# SCH_n2_pdb_v4_2022-03-22.net
KiCad netlist of a schematic drawn in EasyEDA
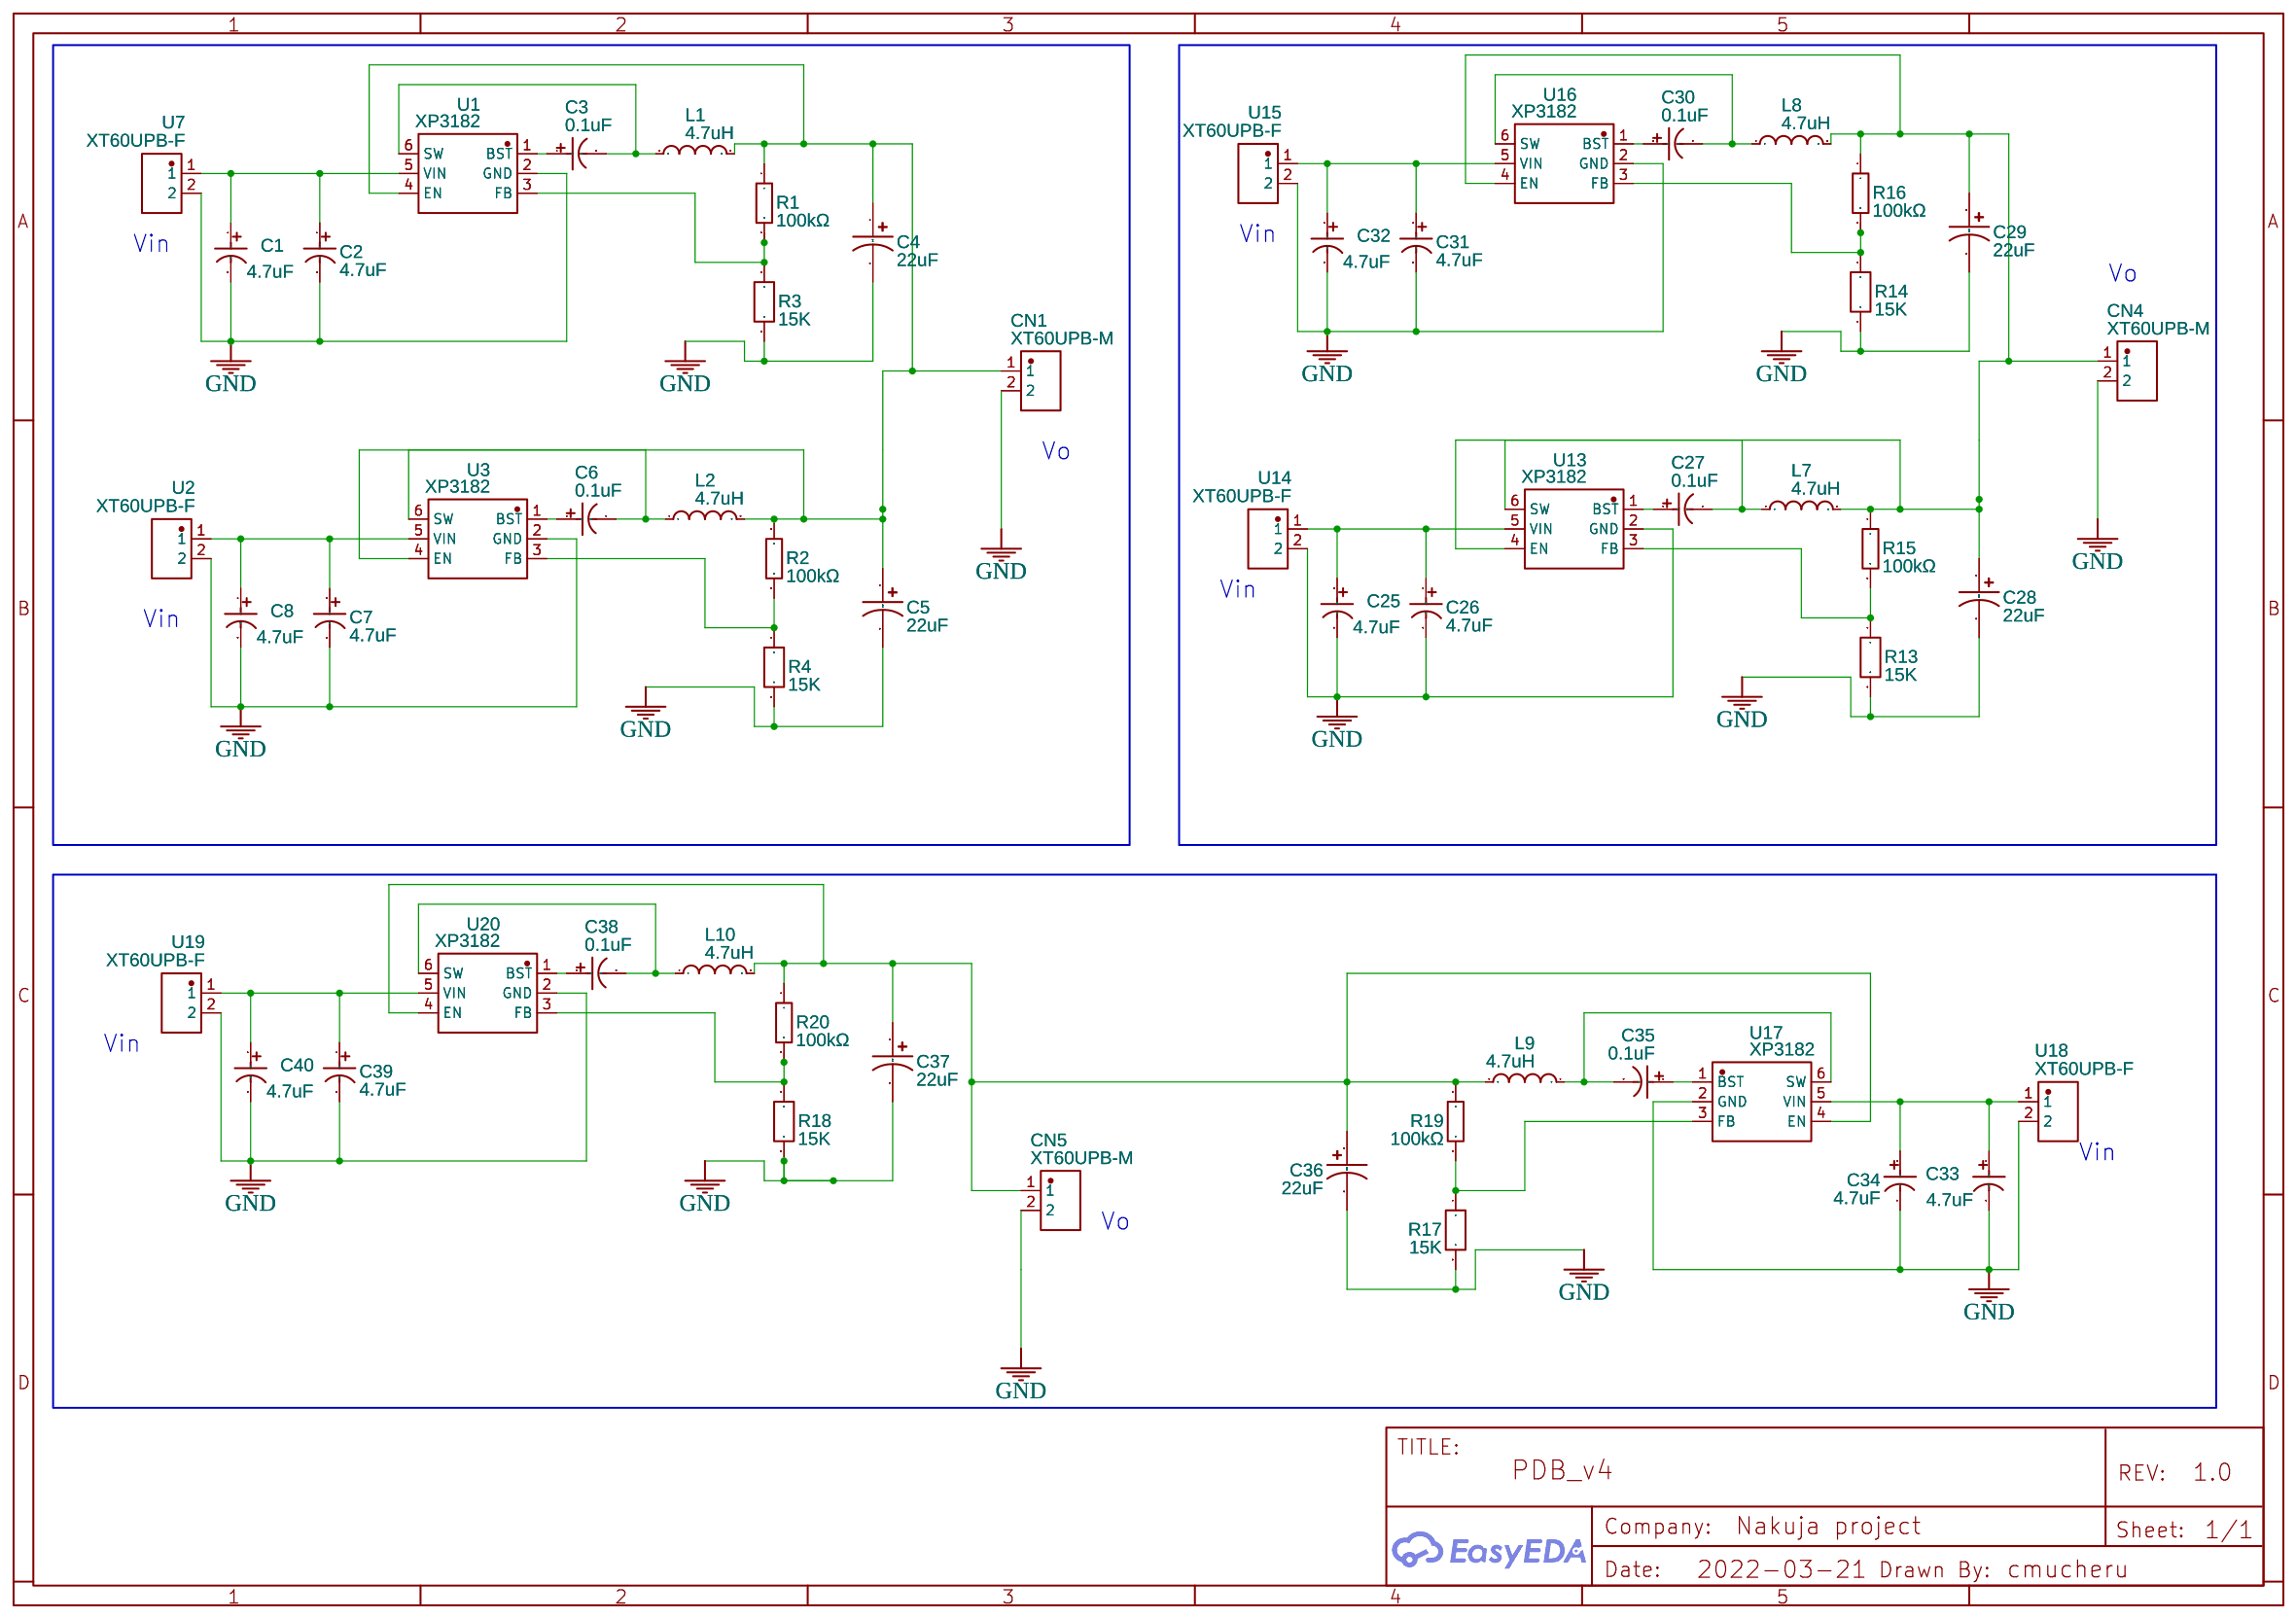
[diagram p0: schematic sheet]

(export (version "E")
  (design (tool "Eeschema 10.0.6"))
  (components
    (comp (ref "C1")
      (value "4.7uF")
      (fields
        (field (name "BOM_Manufacturer Part") "ERK2GM4R7F09OT")
        (field (name "BOM_Supplier Part") "C112499")
      )
      (libsource (lib "") (part "ERK2GM4R7F09OT"))
    )
    (comp (ref "C2")
      (value "4.7uF")
      (fields
        (field (name "BOM_Manufacturer Part") "ERK2GM4R7F09OT")
        (field (name "BOM_Supplier Part") "C112499")
      )
      (libsource (lib "") (part "ERK2GM4R7F09OT"))
    )
    (comp (ref "C3")
      (value "0.1uF")
      (fields
        (field (name "BOM_Manufacturer Part") "0.1uF 50V 4*5 Black high frequency")
        (field (name "BOM_Supplier Part") "C45093")
      )
      (libsource (lib "") (part "0.1uF 50V 4*5 Black high frequency"))
    )
    (comp (ref "C4")
      (value "22uF")
      (fields
        (field (name "BOM_Manufacturer Part") "400AX22MEFC12.5X16")
        (field (name "BOM_Supplier Part") "C473193")
      )
      (libsource (lib "") (part "400AX22MEFC12.5X16"))
    )
    (comp (ref "C5")
      (value "22uF")
      (fields
        (field (name "BOM_Manufacturer Part") "400AX22MEFC12.5X16")
        (field (name "BOM_Supplier Part") "C473193")
      )
      (libsource (lib "") (part "400AX22MEFC12.5X16"))
    )
    (comp (ref "C6")
      (value "0.1uF")
      (fields
        (field (name "BOM_Manufacturer Part") "0.1uF 50V 4*5 Black high frequency")
        (field (name "BOM_Supplier Part") "C45093")
      )
      (libsource (lib "") (part "0.1uF 50V 4*5 Black high frequency"))
    )
    (comp (ref "C7")
      (value "4.7uF")
      (fields
        (field (name "BOM_Manufacturer Part") "ERK2GM4R7F09OT")
        (field (name "BOM_Supplier Part") "C112499")
      )
      (libsource (lib "") (part "ERK2GM4R7F09OT"))
    )
    (comp (ref "C8")
      (value "4.7uF")
      (fields
        (field (name "BOM_Manufacturer Part") "ERK2GM4R7F09OT")
        (field (name "BOM_Supplier Part") "C112499")
      )
      (libsource (lib "") (part "ERK2GM4R7F09OT"))
    )
    (comp (ref "C25")
      (value "4.7uF")
      (fields
        (field (name "BOM_Manufacturer Part") "ERK2GM4R7F09OT")
        (field (name "BOM_Supplier Part") "C112499")
      )
      (libsource (lib "") (part "ERK2GM4R7F09OT"))
    )
    (comp (ref "C26")
      (value "4.7uF")
      (fields
        (field (name "BOM_Manufacturer Part") "ERK2GM4R7F09OT")
        (field (name "BOM_Supplier Part") "C112499")
      )
      (libsource (lib "") (part "ERK2GM4R7F09OT"))
    )
    (comp (ref "C27")
      (value "0.1uF")
      (fields
        (field (name "BOM_Manufacturer Part") "0.1uF 50V 4*5 Black high frequency")
        (field (name "BOM_Supplier Part") "C45093")
      )
      (libsource (lib "") (part "0.1uF 50V 4*5 Black high frequency"))
    )
    (comp (ref "C28")
      (value "22uF")
      (fields
        (field (name "BOM_Manufacturer Part") "400AX22MEFC12.5X16")
        (field (name "BOM_Supplier Part") "C473193")
      )
      (libsource (lib "") (part "400AX22MEFC12.5X16"))
    )
    (comp (ref "C29")
      (value "22uF")
      (fields
        (field (name "BOM_Manufacturer Part") "400AX22MEFC12.5X16")
        (field (name "BOM_Supplier Part") "C473193")
      )
      (libsource (lib "") (part "400AX22MEFC12.5X16"))
    )
    (comp (ref "C30")
      (value "0.1uF")
      (fields
        (field (name "BOM_Manufacturer Part") "0.1uF 50V 4*5 Black high frequency")
        (field (name "BOM_Supplier Part") "C45093")
      )
      (libsource (lib "") (part "0.1uF 50V 4*5 Black high frequency"))
    )
    (comp (ref "C31")
      (value "4.7uF")
      (fields
        (field (name "BOM_Manufacturer Part") "ERK2GM4R7F09OT")
        (field (name "BOM_Supplier Part") "C112499")
      )
      (libsource (lib "") (part "ERK2GM4R7F09OT"))
    )
    (comp (ref "C32")
      (value "4.7uF")
      (fields
        (field (name "BOM_Manufacturer Part") "ERK2GM4R7F09OT")
        (field (name "BOM_Supplier Part") "C112499")
      )
      (libsource (lib "") (part "ERK2GM4R7F09OT"))
    )
    (comp (ref "C33")
      (value "4.7uF")
      (fields
        (field (name "BOM_Manufacturer Part") "ERK2GM4R7F09OT")
        (field (name "BOM_Supplier Part") "C112499")
      )
      (libsource (lib "") (part "ERK2GM4R7F09OT_1"))
    )
    (comp (ref "C34")
      (value "4.7uF")
      (fields
        (field (name "BOM_Manufacturer Part") "ERK2GM4R7F09OT")
        (field (name "BOM_Supplier Part") "C112499")
      )
      (libsource (lib "") (part "ERK2GM4R7F09OT_1"))
    )
    (comp (ref "C35")
      (value "0.1uF")
      (fields
        (field (name "BOM_Manufacturer Part") "0.1uF 50V 4*5 Black high frequency")
        (field (name "BOM_Supplier Part") "C45093")
      )
      (libsource (lib "") (part "0.1uF 50V 4*5 Black high frequency_1"))
    )
    (comp (ref "C36")
      (value "22uF")
      (fields
        (field (name "BOM_Manufacturer Part") "400AX22MEFC12.5X16")
        (field (name "BOM_Supplier Part") "C473193")
      )
      (libsource (lib "") (part "400AX22MEFC12.5X16_1"))
    )
    (comp (ref "C37")
      (value "22uF")
      (fields
        (field (name "BOM_Manufacturer Part") "400AX22MEFC12.5X16")
        (field (name "BOM_Supplier Part") "C473193")
      )
      (libsource (lib "") (part "400AX22MEFC12.5X16"))
    )
    (comp (ref "C38")
      (value "0.1uF")
      (fields
        (field (name "BOM_Manufacturer Part") "0.1uF 50V 4*5 Black high frequency")
        (field (name "BOM_Supplier Part") "C45093")
      )
      (libsource (lib "") (part "0.1uF 50V 4*5 Black high frequency"))
    )
    (comp (ref "C39")
      (value "4.7uF")
      (fields
        (field (name "BOM_Manufacturer Part") "ERK2GM4R7F09OT")
        (field (name "BOM_Supplier Part") "C112499")
      )
      (libsource (lib "") (part "ERK2GM4R7F09OT"))
    )
    (comp (ref "C40")
      (value "4.7uF")
      (fields
        (field (name "BOM_Manufacturer Part") "ERK2GM4R7F09OT")
        (field (name "BOM_Supplier Part") "C112499")
      )
      (libsource (lib "") (part "ERK2GM4R7F09OT"))
    )
    (comp (ref "CN1")
      (value "XT60UPB-M")
      (fields (field (name "BOM_Supplier Part") "C2918078"))
      (libsource (lib "") (part "XT60UPB-M"))
    )
    (comp (ref "CN4")
      (value "XT60UPB-M")
      (fields (field (name "BOM_Supplier Part") "C2918078"))
      (libsource (lib "") (part "XT60UPB-M"))
    )
    (comp (ref "CN5")
      (value "XT60UPB-M")
      (fields (field (name "BOM_Supplier Part") "C2918078"))
      (libsource (lib "") (part "XT60UPB-M"))
    )
    (comp (ref "L1")
      (value "4.7uH")
      (fields
        (field (name "BOM_Manufacturer Part") "MCS0530-4R7MN2")
        (field (name "BOM_Supplier Part") "C2836880")
      )
      (libsource (lib "") (part "MCS0530-4R7MN2_1"))
    )
    (comp (ref "L2")
      (value "4.7uH")
      (fields
        (field (name "BOM_Manufacturer Part") "MCS0530-4R7MN2")
        (field (name "BOM_Supplier Part") "C2836880")
      )
      (libsource (lib "") (part "MCS0530-4R7MN2_1"))
    )
    (comp (ref "L7")
      (value "4.7uH")
      (fields
        (field (name "BOM_Manufacturer Part") "MCS0530-4R7MN2")
        (field (name "BOM_Supplier Part") "C2836880")
      )
      (libsource (lib "") (part "MCS0530-4R7MN2_1"))
    )
    (comp (ref "L8")
      (value "4.7uH")
      (fields
        (field (name "BOM_Manufacturer Part") "MCS0530-4R7MN2")
        (field (name "BOM_Supplier Part") "C2836880")
      )
      (libsource (lib "") (part "MCS0530-4R7MN2_1"))
    )
    (comp (ref "L9")
      (value "4.7uH")
      (fields
        (field (name "BOM_Manufacturer Part") "MCS0530-4R7MN2")
        (field (name "BOM_Supplier Part") "C2836880")
      )
      (libsource (lib "") (part "MCS0530-4R7MN2"))
    )
    (comp (ref "L10")
      (value "4.7uH")
      (fields
        (field (name "BOM_Manufacturer Part") "MCS0530-4R7MN2")
        (field (name "BOM_Supplier Part") "C2836880")
      )
      (libsource (lib "") (part "MCS0530-4R7MN2_1"))
    )
    (comp (ref "R1")
      (value "100kΩ")
      (fields
        (field (name "BOM_Manufacturer Part") "AR02BTD1003")
        (field (name "BOM_Supplier Part") "C319965")
      )
      (libsource (lib "") (part "AR02BTD1003"))
    )
    (comp (ref "R2")
      (value "100kΩ")
      (fields
        (field (name "BOM_Manufacturer Part") "AR02BTD1003")
        (field (name "BOM_Supplier Part") "C319965")
      )
      (libsource (lib "") (part "AR02BTD1003"))
    )
    (comp (ref "R3")
      (value "15K")
      (fields
        (field (name "BOM_Manufacturer Part") "TC0525D1502T5E")
        (field (name "BOM_Supplier Part") "C44536")
      )
      (libsource (lib "") (part "TC0525D1502T5E_C44536"))
    )
    (comp (ref "R4")
      (value "15K")
      (fields
        (field (name "BOM_Manufacturer Part") "TC0525D1502T5E")
        (field (name "BOM_Supplier Part") "C44536")
      )
      (libsource (lib "") (part "TC0525D1502T5E_C44536"))
    )
    (comp (ref "R13")
      (value "15K")
      (fields
        (field (name "BOM_Manufacturer Part") "TC0525D1502T5E")
        (field (name "BOM_Supplier Part") "C44536")
      )
      (libsource (lib "") (part "TC0525D1502T5E_C44536"))
    )
    (comp (ref "R14")
      (value "15K")
      (fields
        (field (name "BOM_Manufacturer Part") "TC0525D1502T5E")
        (field (name "BOM_Supplier Part") "C44536")
      )
      (libsource (lib "") (part "TC0525D1502T5E_C44536"))
    )
    (comp (ref "R15")
      (value "100kΩ")
      (fields
        (field (name "BOM_Manufacturer Part") "AR02BTD1003")
        (field (name "BOM_Supplier Part") "C319965")
      )
      (libsource (lib "") (part "AR02BTD1003"))
    )
    (comp (ref "R16")
      (value "100kΩ")
      (fields
        (field (name "BOM_Manufacturer Part") "AR02BTD1003")
        (field (name "BOM_Supplier Part") "C319965")
      )
      (libsource (lib "") (part "AR02BTD1003"))
    )
    (comp (ref "R17")
      (value "15K")
      (fields
        (field (name "BOM_Manufacturer Part") "TC0525D1502T5E")
        (field (name "BOM_Supplier Part") "C44536")
      )
      (libsource (lib "") (part "TC0525D1502T5E_C44536"))
    )
    (comp (ref "R18")
      (value "15K")
      (fields
        (field (name "BOM_Manufacturer Part") "TC0525D1502T5E")
        (field (name "BOM_Supplier Part") "C44536")
      )
      (libsource (lib "") (part "TC0525D1502T5E_C44536"))
    )
    (comp (ref "R19")
      (value "100kΩ")
      (fields
        (field (name "BOM_Manufacturer Part") "AR02BTD1003")
        (field (name "BOM_Supplier Part") "C319965")
      )
      (libsource (lib "") (part "AR02BTD1003"))
    )
    (comp (ref "R20")
      (value "100kΩ")
      (fields
        (field (name "BOM_Manufacturer Part") "AR02BTD1003")
        (field (name "BOM_Supplier Part") "C319965")
      )
      (libsource (lib "") (part "AR02BTD1003"))
    )
    (comp (ref "U1")
      (value "XP3182")
      (fields (field (name "BOM_Supplier Part") "C2802261"))
      (libsource (lib "") (part "XP3182"))
    )
    (comp (ref "U2")
      (value "XT60UPB-F")
      (fields (field (name "BOM_Supplier Part") "C9900007500"))
      (libsource (lib "") (part "XT60UPB-F"))
    )
    (comp (ref "U3")
      (value "XP3182")
      (fields (field (name "BOM_Supplier Part") "C2802261"))
      (libsource (lib "") (part "XP3182"))
    )
    (comp (ref "U7")
      (value "XT60UPB-F")
      (fields (field (name "BOM_Supplier Part") "C9900007500"))
      (libsource (lib "") (part "XT60UPB-F"))
    )
    (comp (ref "U13")
      (value "XP3182")
      (fields (field (name "BOM_Supplier Part") "C2802261"))
      (libsource (lib "") (part "XP3182"))
    )
    (comp (ref "U14")
      (value "XT60UPB-F")
      (fields (field (name "BOM_Supplier Part") "C9900007500"))
      (libsource (lib "") (part "XT60UPB-F"))
    )
    (comp (ref "U15")
      (value "XT60UPB-F")
      (fields (field (name "BOM_Supplier Part") "C9900007500"))
      (libsource (lib "") (part "XT60UPB-F"))
    )
    (comp (ref "U16")
      (value "XP3182")
      (fields (field (name "BOM_Supplier Part") "C2802261"))
      (libsource (lib "") (part "XP3182"))
    )
    (comp (ref "U17")
      (value "XP3182")
      (fields (field (name "BOM_Supplier Part") "C2802261"))
      (libsource (lib "") (part "XP3182_1"))
    )
    (comp (ref "U18")
      (value "XT60UPB-F")
      (fields (field (name "BOM_Supplier Part") "C9900007500"))
      (libsource (lib "") (part "XT60UPB-F_1"))
    )
    (comp (ref "U19")
      (value "XT60UPB-F")
      (fields (field (name "BOM_Supplier Part") "C9900007500"))
      (libsource (lib "") (part "XT60UPB-F"))
    )
    (comp (ref "U20")
      (value "XP3182")
      (fields (field (name "BOM_Supplier Part") "C2802261"))
      (libsource (lib "") (part "XP3182"))
    )
  )
  (nets
    (net (code "1") (name "GND") (class "Default")
      (node (ref "C1") (pin "2") (pinfunction "2_2") (pintype "input"))
      (node (ref "C2") (pin "2") (pinfunction "2_2") (pintype "input"))
      (node (ref "C25") (pin "2") (pinfunction "2_2") (pintype "input"))
      (node (ref "C26") (pin "2") (pinfunction "2_2") (pintype "input"))
      (node (ref "C28") (pin "2") (pinfunction "2_2") (pintype "unspecified"))
      (node (ref "C29") (pin "2") (pinfunction "2_2") (pintype "unspecified"))
      (node (ref "C31") (pin "2") (pinfunction "2_2") (pintype "input"))
      (node (ref "C32") (pin "2") (pinfunction "2_2") (pintype "input"))
      (node (ref "C33") (pin "2") (pinfunction "2_2") (pintype "input"))
      (node (ref "C34") (pin "2") (pinfunction "2_2") (pintype "input"))
      (node (ref "C36") (pin "2") (pinfunction "2_2") (pintype "unspecified"))
      (node (ref "C37") (pin "2") (pinfunction "2_2") (pintype "unspecified"))
      (node (ref "C39") (pin "2") (pinfunction "2_2") (pintype "input"))
      (node (ref "C4") (pin "2") (pinfunction "2_2") (pintype "unspecified"))
      (node (ref "C40") (pin "2") (pinfunction "2_2") (pintype "input"))
      (node (ref "C5") (pin "2") (pinfunction "2_2") (pintype "unspecified"))
      (node (ref "C7") (pin "2") (pinfunction "2_2") (pintype "input"))
      (node (ref "C8") (pin "2") (pinfunction "2_2") (pintype "input"))
      (node (ref "CN1") (pin "2") (pinfunction "2_2") (pintype "unspecified"))
      (node (ref "CN4") (pin "2") (pinfunction "2_2") (pintype "unspecified"))
      (node (ref "CN5") (pin "2") (pinfunction "2_2") (pintype "unspecified"))
      (node (ref "R13") (pin "2") (pinfunction "2_2") (pintype "unspecified"))
      (node (ref "R14") (pin "2") (pinfunction "2_2") (pintype "unspecified"))
      (node (ref "R17") (pin "2") (pinfunction "2_2") (pintype "unspecified"))
      (node (ref "R18") (pin "2") (pinfunction "2_2") (pintype "unspecified"))
      (node (ref "R3") (pin "2") (pinfunction "2_2") (pintype "unspecified"))
      (node (ref "R4") (pin "2") (pinfunction "2_2") (pintype "unspecified"))
      (node (ref "U1") (pin "2") (pinfunction "GND_2") (pintype "unspecified"))
      (node (ref "U13") (pin "2") (pinfunction "GND_2") (pintype "unspecified"))
      (node (ref "U14") (pin "2") (pinfunction "2_2") (pintype "unspecified"))
      (node (ref "U15") (pin "2") (pinfunction "2_2") (pintype "unspecified"))
      (node (ref "U16") (pin "2") (pinfunction "GND_2") (pintype "unspecified"))
      (node (ref "U17") (pin "2") (pinfunction "GND_2") (pintype "unspecified"))
      (node (ref "U18") (pin "2") (pinfunction "2_2") (pintype "unspecified"))
      (node (ref "U19") (pin "2") (pinfunction "2_2") (pintype "unspecified"))
      (node (ref "U2") (pin "2") (pinfunction "2_2") (pintype "unspecified"))
      (node (ref "U20") (pin "2") (pinfunction "GND_2") (pintype "unspecified"))
      (node (ref "U3") (pin "2") (pinfunction "GND_2") (pintype "unspecified"))
      (node (ref "U7") (pin "2") (pinfunction "2_2") (pintype "unspecified"))
    )
    (net (code "2") (name "Net-(U1-BST)") (class "Default")
      (node (ref "C3") (pin "1") (pinfunction "1_1") (pintype "input"))
      (node (ref "U1") (pin "1") (pinfunction "BST_1") (pintype "unspecified"))
    )
    (net (code "3") (name "Net-(U1-EN)") (class "Default")
      (node (ref "C4") (pin "1") (pinfunction "1_1") (pintype "unspecified"))
      (node (ref "C5") (pin "1") (pinfunction "1_1") (pintype "unspecified"))
      (node (ref "CN1") (pin "1") (pinfunction "1_1") (pintype "unspecified"))
      (node (ref "L1") (pin "2") (pinfunction "2_2") (pintype "unspecified"))
      (node (ref "L2") (pin "2") (pinfunction "2_2") (pintype "unspecified"))
      (node (ref "R1") (pin "1") (pinfunction "1_1") (pintype "unspecified"))
      (node (ref "R2") (pin "1") (pinfunction "1_1") (pintype "unspecified"))
      (node (ref "U1") (pin "4") (pinfunction "EN_4") (pintype "unspecified"))
      (node (ref "U3") (pin "4") (pinfunction "EN_4") (pintype "unspecified"))
    )
    (net (code "4") (name "Net-(U1-FB)") (class "Default")
      (node (ref "R1") (pin "2") (pinfunction "2_2") (pintype "unspecified"))
      (node (ref "R3") (pin "1") (pinfunction "1_1") (pintype "unspecified"))
      (node (ref "U1") (pin "3") (pinfunction "FB_3") (pintype "unspecified"))
    )
    (net (code "5") (name "Net-(U1-SW)") (class "Default")
      (node (ref "C3") (pin "2") (pinfunction "2_2") (pintype "input"))
      (node (ref "L1") (pin "1") (pinfunction "1_1") (pintype "unspecified"))
      (node (ref "U1") (pin "6") (pinfunction "SW_6") (pintype "unspecified"))
    )
    (net (code "6") (name "Net-(U1-VIN)") (class "Default")
      (node (ref "C1") (pin "1") (pinfunction "1_1") (pintype "input"))
      (node (ref "C2") (pin "1") (pinfunction "1_1") (pintype "input"))
      (node (ref "U1") (pin "5") (pinfunction "VIN_5") (pintype "unspecified"))
      (node (ref "U7") (pin "1") (pinfunction "1_1") (pintype "unspecified"))
    )
    (net (code "7") (name "Net-(U3-BST)") (class "Default")
      (node (ref "C6") (pin "1") (pinfunction "1_1") (pintype "input"))
      (node (ref "U3") (pin "1") (pinfunction "BST_1") (pintype "unspecified"))
    )
    (net (code "8") (name "Net-(U3-FB)") (class "Default")
      (node (ref "R2") (pin "2") (pinfunction "2_2") (pintype "unspecified"))
      (node (ref "R4") (pin "1") (pinfunction "1_1") (pintype "unspecified"))
      (node (ref "U3") (pin "3") (pinfunction "FB_3") (pintype "unspecified"))
    )
    (net (code "9") (name "Net-(U3-SW)") (class "Default")
      (node (ref "C6") (pin "2") (pinfunction "2_2") (pintype "input"))
      (node (ref "L2") (pin "1") (pinfunction "1_1") (pintype "unspecified"))
      (node (ref "U3") (pin "6") (pinfunction "SW_6") (pintype "unspecified"))
    )
    (net (code "10") (name "Net-(U3-VIN)") (class "Default")
      (node (ref "C7") (pin "1") (pinfunction "1_1") (pintype "input"))
      (node (ref "C8") (pin "1") (pinfunction "1_1") (pintype "input"))
      (node (ref "U2") (pin "1") (pinfunction "1_1") (pintype "unspecified"))
      (node (ref "U3") (pin "5") (pinfunction "VIN_5") (pintype "unspecified"))
    )
    (net (code "11") (name "Net-(U13-BST)") (class "Default")
      (node (ref "C27") (pin "1") (pinfunction "1_1") (pintype "input"))
      (node (ref "U13") (pin "1") (pinfunction "BST_1") (pintype "unspecified"))
    )
    (net (code "12") (name "Net-(U13-EN)") (class "Default")
      (node (ref "C28") (pin "1") (pinfunction "1_1") (pintype "unspecified"))
      (node (ref "C29") (pin "1") (pinfunction "1_1") (pintype "unspecified"))
      (node (ref "CN4") (pin "1") (pinfunction "1_1") (pintype "unspecified"))
      (node (ref "L7") (pin "2") (pinfunction "2_2") (pintype "unspecified"))
      (node (ref "L8") (pin "2") (pinfunction "2_2") (pintype "unspecified"))
      (node (ref "R15") (pin "1") (pinfunction "1_1") (pintype "unspecified"))
      (node (ref "R16") (pin "1") (pinfunction "1_1") (pintype "unspecified"))
      (node (ref "U13") (pin "4") (pinfunction "EN_4") (pintype "unspecified"))
      (node (ref "U16") (pin "4") (pinfunction "EN_4") (pintype "unspecified"))
    )
    (net (code "13") (name "Net-(U13-FB)") (class "Default")
      (node (ref "R13") (pin "1") (pinfunction "1_1") (pintype "unspecified"))
      (node (ref "R15") (pin "2") (pinfunction "2_2") (pintype "unspecified"))
      (node (ref "U13") (pin "3") (pinfunction "FB_3") (pintype "unspecified"))
    )
    (net (code "14") (name "Net-(U13-SW)") (class "Default")
      (node (ref "C27") (pin "2") (pinfunction "2_2") (pintype "input"))
      (node (ref "L7") (pin "1") (pinfunction "1_1") (pintype "unspecified"))
      (node (ref "U13") (pin "6") (pinfunction "SW_6") (pintype "unspecified"))
    )
    (net (code "15") (name "Net-(U13-VIN)") (class "Default")
      (node (ref "C25") (pin "1") (pinfunction "1_1") (pintype "input"))
      (node (ref "C26") (pin "1") (pinfunction "1_1") (pintype "input"))
      (node (ref "U13") (pin "5") (pinfunction "VIN_5") (pintype "unspecified"))
      (node (ref "U14") (pin "1") (pinfunction "1_1") (pintype "unspecified"))
    )
    (net (code "16") (name "Net-(U16-BST)") (class "Default")
      (node (ref "C30") (pin "1") (pinfunction "1_1") (pintype "input"))
      (node (ref "U16") (pin "1") (pinfunction "BST_1") (pintype "unspecified"))
    )
    (net (code "17") (name "Net-(U16-FB)") (class "Default")
      (node (ref "R14") (pin "1") (pinfunction "1_1") (pintype "unspecified"))
      (node (ref "R16") (pin "2") (pinfunction "2_2") (pintype "unspecified"))
      (node (ref "U16") (pin "3") (pinfunction "FB_3") (pintype "unspecified"))
    )
    (net (code "18") (name "Net-(U16-SW)") (class "Default")
      (node (ref "C30") (pin "2") (pinfunction "2_2") (pintype "input"))
      (node (ref "L8") (pin "1") (pinfunction "1_1") (pintype "unspecified"))
      (node (ref "U16") (pin "6") (pinfunction "SW_6") (pintype "unspecified"))
    )
    (net (code "19") (name "Net-(U16-VIN)") (class "Default")
      (node (ref "C31") (pin "1") (pinfunction "1_1") (pintype "input"))
      (node (ref "C32") (pin "1") (pinfunction "1_1") (pintype "input"))
      (node (ref "U15") (pin "1") (pinfunction "1_1") (pintype "unspecified"))
      (node (ref "U16") (pin "5") (pinfunction "VIN_5") (pintype "unspecified"))
    )
    (net (code "20") (name "Net-(U17-BST)") (class "Default")
      (node (ref "C35") (pin "1") (pinfunction "1_1") (pintype "input"))
      (node (ref "U17") (pin "1") (pinfunction "BST_1") (pintype "unspecified"))
    )
    (net (code "21") (name "Net-(U17-EN)") (class "Default")
      (node (ref "C36") (pin "1") (pinfunction "1_1") (pintype "unspecified"))
      (node (ref "C37") (pin "1") (pinfunction "1_1") (pintype "unspecified"))
      (node (ref "CN5") (pin "1") (pinfunction "1_1") (pintype "unspecified"))
      (node (ref "L10") (pin "2") (pinfunction "2_2") (pintype "unspecified"))
      (node (ref "L9") (pin "2") (pinfunction "2_2") (pintype "unspecified"))
      (node (ref "R19") (pin "1") (pinfunction "1_1") (pintype "unspecified"))
      (node (ref "R20") (pin "1") (pinfunction "1_1") (pintype "unspecified"))
      (node (ref "U17") (pin "4") (pinfunction "EN_4") (pintype "unspecified"))
      (node (ref "U20") (pin "4") (pinfunction "EN_4") (pintype "unspecified"))
    )
    (net (code "22") (name "Net-(U17-FB)") (class "Default")
      (node (ref "R17") (pin "1") (pinfunction "1_1") (pintype "unspecified"))
      (node (ref "R19") (pin "2") (pinfunction "2_2") (pintype "unspecified"))
      (node (ref "U17") (pin "3") (pinfunction "FB_3") (pintype "unspecified"))
    )
    (net (code "23") (name "Net-(U17-SW)") (class "Default")
      (node (ref "C35") (pin "2") (pinfunction "2_2") (pintype "input"))
      (node (ref "L9") (pin "1") (pinfunction "1_1") (pintype "unspecified"))
      (node (ref "U17") (pin "6") (pinfunction "SW_6") (pintype "unspecified"))
    )
    (net (code "24") (name "Net-(U17-VIN)") (class "Default")
      (node (ref "C33") (pin "1") (pinfunction "1_1") (pintype "input"))
      (node (ref "C34") (pin "1") (pinfunction "1_1") (pintype "input"))
      (node (ref "U17") (pin "5") (pinfunction "VIN_5") (pintype "unspecified"))
      (node (ref "U18") (pin "1") (pinfunction "1_1") (pintype "unspecified"))
    )
    (net (code "25") (name "Net-(U20-BST)") (class "Default")
      (node (ref "C38") (pin "1") (pinfunction "1_1") (pintype "input"))
      (node (ref "U20") (pin "1") (pinfunction "BST_1") (pintype "unspecified"))
    )
    (net (code "26") (name "Net-(U20-FB)") (class "Default")
      (node (ref "R18") (pin "1") (pinfunction "1_1") (pintype "unspecified"))
      (node (ref "R20") (pin "2") (pinfunction "2_2") (pintype "unspecified"))
      (node (ref "U20") (pin "3") (pinfunction "FB_3") (pintype "unspecified"))
    )
    (net (code "27") (name "Net-(U20-SW)") (class "Default")
      (node (ref "C38") (pin "2") (pinfunction "2_2") (pintype "input"))
      (node (ref "L10") (pin "1") (pinfunction "1_1") (pintype "unspecified"))
      (node (ref "U20") (pin "6") (pinfunction "SW_6") (pintype "unspecified"))
    )
    (net (code "28") (name "Net-(U20-VIN)") (class "Default")
      (node (ref "C39") (pin "1") (pinfunction "1_1") (pintype "input"))
      (node (ref "C40") (pin "1") (pinfunction "1_1") (pintype "input"))
      (node (ref "U19") (pin "1") (pinfunction "1_1") (pintype "unspecified"))
      (node (ref "U20") (pin "5") (pinfunction "VIN_5") (pintype "unspecified"))
    )
  )
)
